# Regulators.net
KiCad netlist of a schematic drawn in Altium Designer
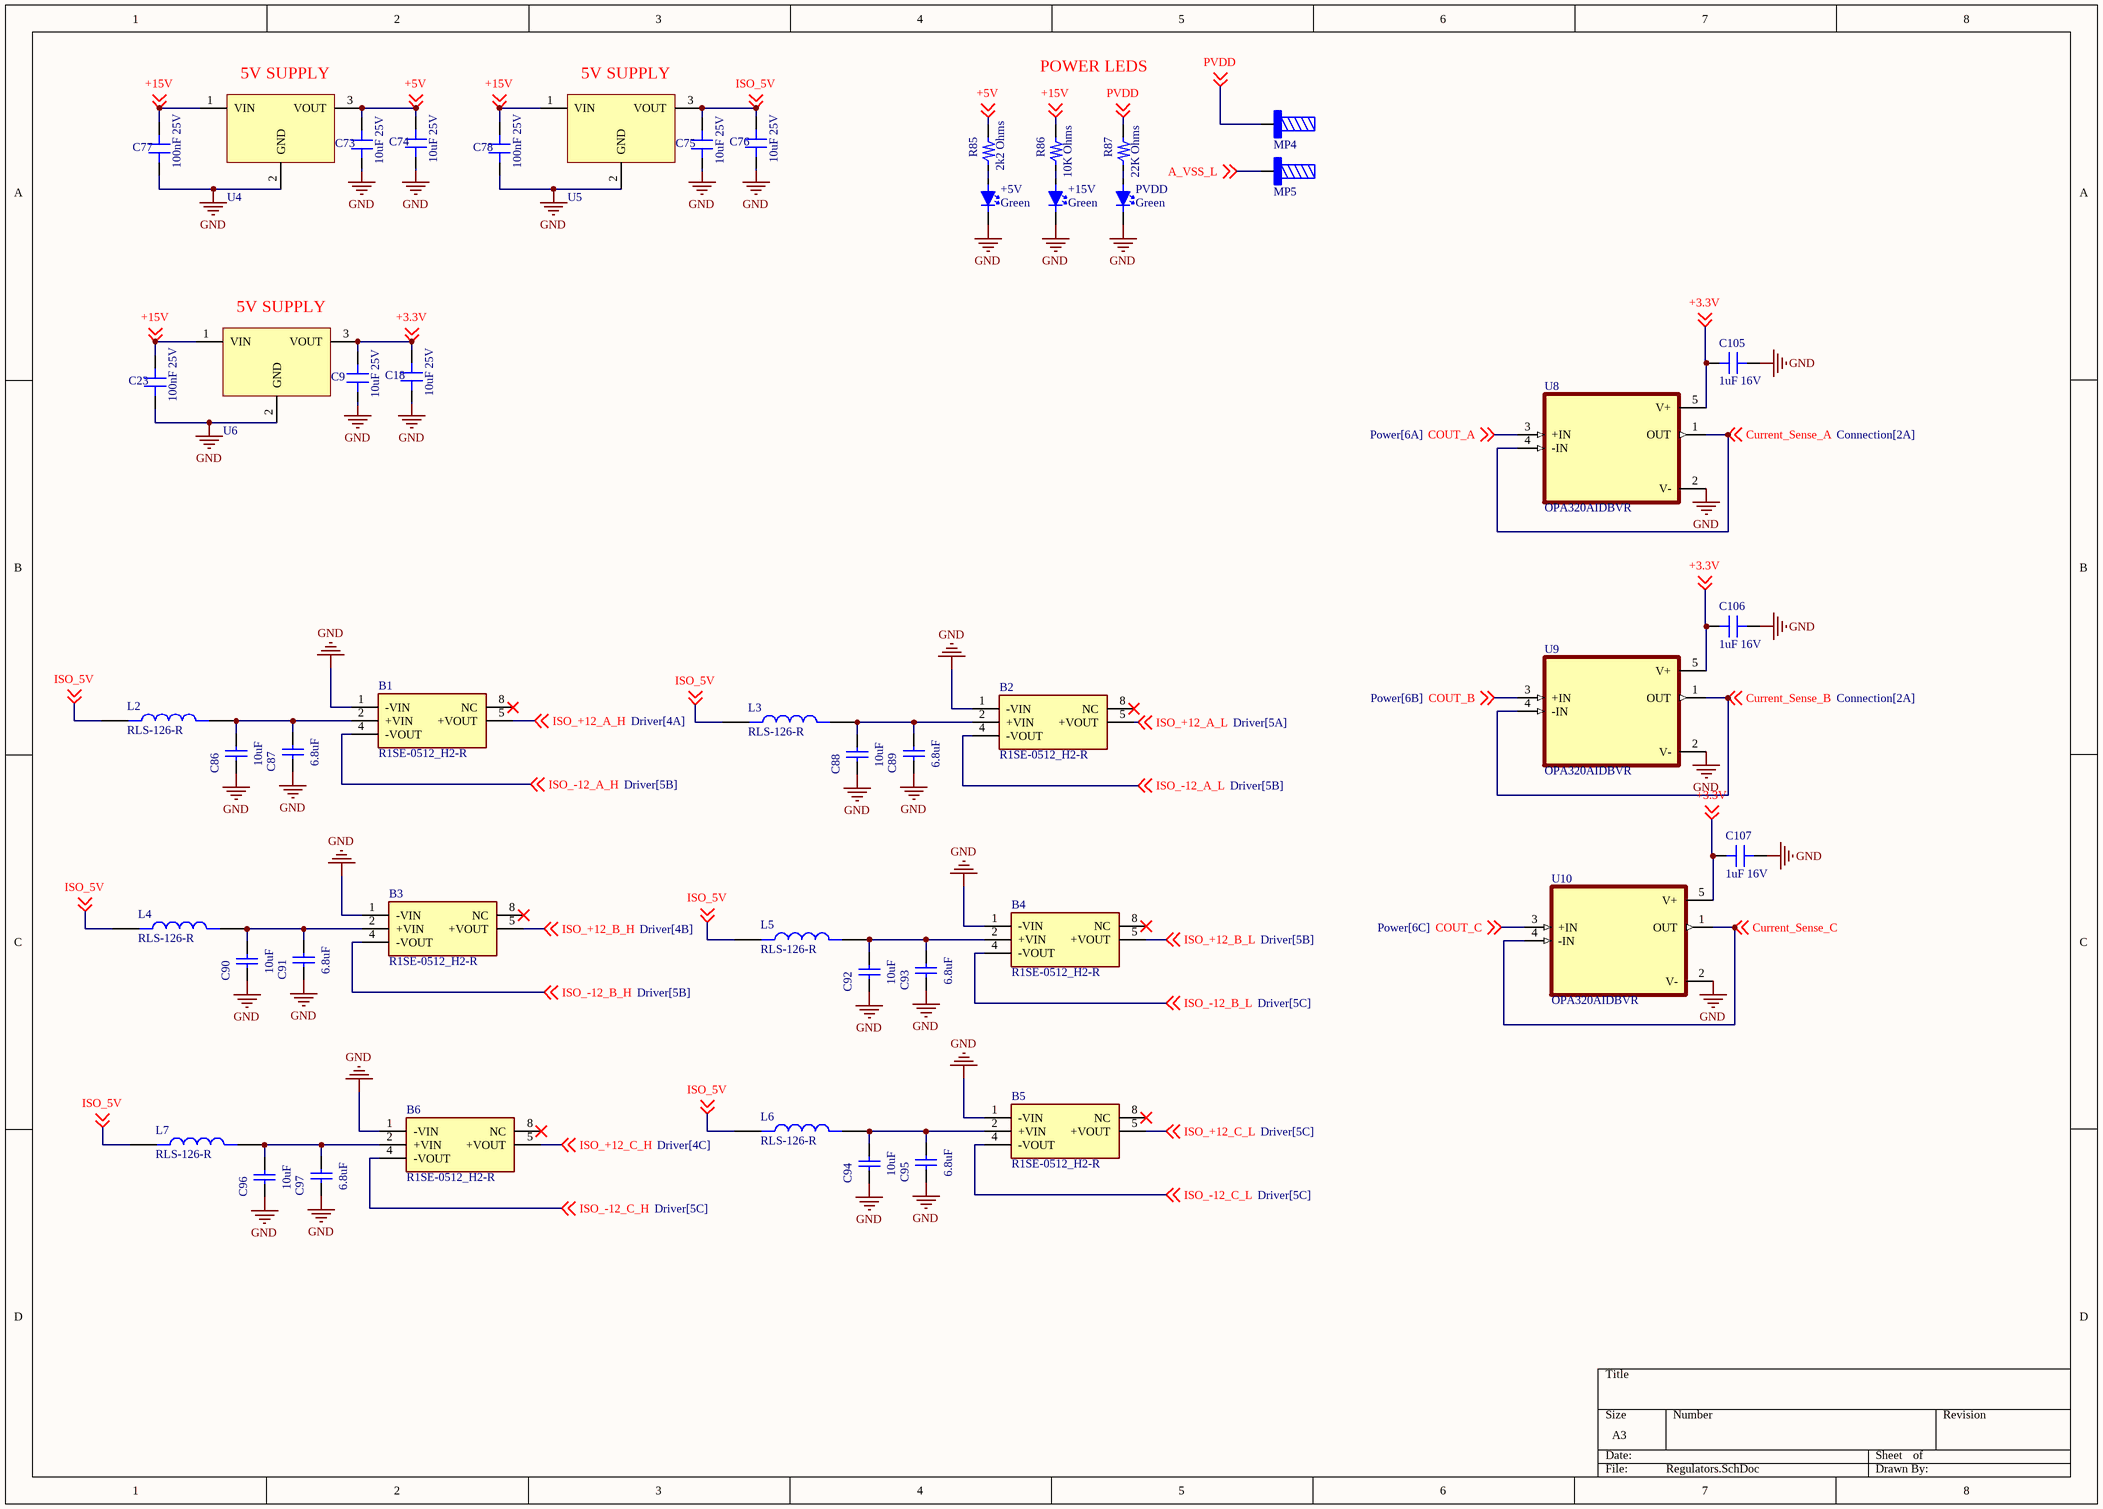
[diagram p0: Regulators.SchDoc]

(export (version "E")
  (design (tool "Eeschema 10.0.6"))
  (components
    (comp (ref "+5V")
      (value "Green")
      (footprint "0805LED")
      (description "0805")
      (libsource (lib "HidroanaSCHLib") (part "LED"))
    )
    (comp (ref "+15V")
      (value "Green")
      (footprint "0805LED")
      (description "0805")
      (libsource (lib "HidroanaSCHLib") (part "LED"))
    )
    (comp (ref "B1")
      (value "R1SE-0512_H2-R")
      (footprint "R1SE3305H2R")
      (description "RECOM POWER - R1SE-0512/H2-R - DC-DC CONVERTER, 12V, 0.084A, SMD")
      (fields
        (field (name "MANUFACTURER_PART_NUMBER") "R1SE-0512/H2-R")
        (field (name "MOUSER PART NUMBER") "919-R1SE-0512/H2-R")
      )
      (libsource (lib "R1SE-0512_H2-R") (part "R1SE-0512_H2-R"))
    )
    (comp (ref "B2")
      (value "R1SE-0512_H2-R")
      (footprint "R1SE3305H2R")
      (description "RECOM POWER - R1SE-0512/H2-R - DC-DC CONVERTER, 12V, 0.084A, SMD")
      (fields
        (field (name "MANUFACTURER_PART_NUMBER") "R1SE-0512/H2-R")
        (field (name "MOUSER PART NUMBER") "919-R1SE-0512/H2-R")
      )
      (libsource (lib "R1SE-0512_H2-R") (part "R1SE-0512_H2-R"))
    )
    (comp (ref "B3")
      (value "R1SE-0512_H2-R")
      (footprint "R1SE3305H2R")
      (description "RECOM POWER - R1SE-0512/H2-R - DC-DC CONVERTER, 12V, 0.084A, SMD")
      (fields
        (field (name "MANUFACTURER_PART_NUMBER") "R1SE-0512/H2-R")
        (field (name "MOUSER PART NUMBER") "919-R1SE-0512/H2-R")
      )
      (libsource (lib "R1SE-0512_H2-R") (part "R1SE-0512_H2-R"))
    )
    (comp (ref "B4")
      (value "R1SE-0512_H2-R")
      (footprint "R1SE3305H2R")
      (description "RECOM POWER - R1SE-0512/H2-R - DC-DC CONVERTER, 12V, 0.084A, SMD")
      (fields
        (field (name "MANUFACTURER_PART_NUMBER") "R1SE-0512/H2-R")
        (field (name "MOUSER PART NUMBER") "919-R1SE-0512/H2-R")
      )
      (libsource (lib "R1SE-0512_H2-R") (part "R1SE-0512_H2-R"))
    )
    (comp (ref "B5")
      (value "R1SE-0512_H2-R")
      (footprint "R1SE3305H2R")
      (description "RECOM POWER - R1SE-0512/H2-R - DC-DC CONVERTER, 12V, 0.084A, SMD")
      (fields
        (field (name "MANUFACTURER_PART_NUMBER") "R1SE-0512/H2-R")
        (field (name "MOUSER PART NUMBER") "919-R1SE-0512/H2-R")
      )
      (libsource (lib "R1SE-0512_H2-R") (part "R1SE-0512_H2-R"))
    )
    (comp (ref "B6")
      (value "R1SE-0512_H2-R")
      (footprint "R1SE3305H2R")
      (description "RECOM POWER - R1SE-0512/H2-R - DC-DC CONVERTER, 12V, 0.084A, SMD")
      (fields
        (field (name "MANUFACTURER_PART_NUMBER") "R1SE-0512/H2-R")
        (field (name "MOUSER PART NUMBER") "919-R1SE-0512/H2-R")
      )
      (libsource (lib "R1SE-0512_H2-R") (part "R1SE-0512_H2-R"))
    )
    (comp (ref "C9")
      (value "10uF 25V")
      (footprint "0603_CAP")
      (description "CL10B105KO8NNNC - MLCC (1608) 0603 1uF 16VDC ±10% X7R")
      (libsource (lib "HidroanaSCHLib") (part "CAP_0603"))
    )
    (comp (ref "C18")
      (value "10uF 25V")
      (footprint "0603_CAP")
      (description "CL10B105KO8NNNC - MLCC (1608) 0603 1uF 16VDC ±10% X7R")
      (libsource (lib "HidroanaSCHLib") (part "CAP_0603"))
    )
    (comp (ref "C23")
      (value "100nF 25V")
      (footprint "0603_CAP")
      (description "CL10B105KO8NNNC - MLCC (1608) 0603 1uF 16VDC ±10% X7R")
      (libsource (lib "HidroanaSCHLib") (part "CAP_0603"))
    )
    (comp (ref "C73")
      (value "10uF 25V")
      (footprint "0603_CAP")
      (description "CL10B105KO8NNNC - MLCC (1608) 0603 1uF 16VDC ±10% X7R")
      (libsource (lib "HidroanaSCHLib") (part "CAP_0603"))
    )
    (comp (ref "C74")
      (value "10uF 25V")
      (footprint "0603_CAP")
      (description "CL10B105KO8NNNC - MLCC (1608) 0603 1uF 16VDC ±10% X7R")
      (libsource (lib "HidroanaSCHLib") (part "CAP_0603"))
    )
    (comp (ref "C75")
      (value "10uF 25V")
      (footprint "0603_CAP")
      (description "CL10B105KO8NNNC - MLCC (1608) 0603 1uF 16VDC ±10% X7R")
      (libsource (lib "HidroanaSCHLib") (part "CAP_0603"))
    )
    (comp (ref "C76")
      (value "10uF 25V")
      (footprint "0603_CAP")
      (description "CL10B105KO8NNNC - MLCC (1608) 0603 1uF 16VDC ±10% X7R")
      (libsource (lib "HidroanaSCHLib") (part "CAP_0603"))
    )
    (comp (ref "C77")
      (value "100nF 25V")
      (footprint "0603_CAP")
      (description "CL10B105KO8NNNC - MLCC (1608) 0603 1uF 16VDC ±10% X7R")
      (libsource (lib "HidroanaSCHLib") (part "CAP_0603"))
    )
    (comp (ref "C78")
      (value "100nF 25V")
      (footprint "0603_CAP")
      (description "CL10B105KO8NNNC - MLCC (1608) 0603 1uF 16VDC ±10% X7R")
      (libsource (lib "HidroanaSCHLib") (part "CAP_0603"))
    )
    (comp (ref "C86")
      (value "10uF")
      (footprint "WCAP-CSGP_0805_L2W1.25H0.6_Reflow")
      (description "WCAP-CSGP Multilayer Ceramic Chip Capacitor, General Purpose, size 0805, NP0, 22pF, 16V")
      (fields
        (field (name "MANUFACTURER PART NUMBER") "885012007012")
        (field (name "MANUFACTURER") "Wurth Elektronik")
      )
      (libsource (lib "Altium_WCAP-CSGP (rev24c)") (part "885012007012"))
    )
    (comp (ref "C87")
      (value "6.8uF")
      (footprint "WCAP-CSGP_0805_L2W1.25H0.6_Reflow")
      (description "WCAP-CSGP Multilayer Ceramic Chip Capacitor, General Purpose, size 0805, NP0, 22pF, 16V")
      (fields
        (field (name "MANUFACTURER PART NUMBER") "885012007012")
        (field (name "MANUFACTURER") "Wurth Elektronik")
      )
      (libsource (lib "Altium_WCAP-CSGP (rev24c)") (part "885012007012"))
    )
    (comp (ref "C88")
      (value "10uF")
      (footprint "WCAP-CSGP_0805_L2W1.25H0.6_Reflow")
      (description "WCAP-CSGP Multilayer Ceramic Chip Capacitor, General Purpose, size 0805, NP0, 22pF, 16V")
      (fields
        (field (name "MANUFACTURER PART NUMBER") "885012007012")
        (field (name "MANUFACTURER") "Wurth Elektronik")
      )
      (libsource (lib "Altium_WCAP-CSGP (rev24c)") (part "885012007012"))
    )
    (comp (ref "C89")
      (value "6.8uF")
      (footprint "WCAP-CSGP_0805_L2W1.25H0.6_Reflow")
      (description "WCAP-CSGP Multilayer Ceramic Chip Capacitor, General Purpose, size 0805, NP0, 22pF, 16V")
      (fields
        (field (name "MANUFACTURER PART NUMBER") "885012007012")
        (field (name "MANUFACTURER") "Wurth Elektronik")
      )
      (libsource (lib "Altium_WCAP-CSGP (rev24c)") (part "885012007012"))
    )
    (comp (ref "C90")
      (value "10uF")
      (footprint "WCAP-CSGP_0805_L2W1.25H0.6_Reflow")
      (description "WCAP-CSGP Multilayer Ceramic Chip Capacitor, General Purpose, size 0805, NP0, 22pF, 16V")
      (fields
        (field (name "MANUFACTURER PART NUMBER") "885012007012")
        (field (name "MANUFACTURER") "Wurth Elektronik")
      )
      (libsource (lib "Altium_WCAP-CSGP (rev24c)") (part "885012007012"))
    )
    (comp (ref "C91")
      (value "6.8uF")
      (footprint "WCAP-CSGP_0805_L2W1.25H0.6_Reflow")
      (description "WCAP-CSGP Multilayer Ceramic Chip Capacitor, General Purpose, size 0805, NP0, 22pF, 16V")
      (fields
        (field (name "MANUFACTURER PART NUMBER") "885012007012")
        (field (name "MANUFACTURER") "Wurth Elektronik")
      )
      (libsource (lib "Altium_WCAP-CSGP (rev24c)") (part "885012007012"))
    )
    (comp (ref "C92")
      (value "10uF")
      (footprint "WCAP-CSGP_0805_L2W1.25H0.6_Reflow")
      (description "WCAP-CSGP Multilayer Ceramic Chip Capacitor, General Purpose, size 0805, NP0, 22pF, 16V")
      (fields
        (field (name "MANUFACTURER PART NUMBER") "885012007012")
        (field (name "MANUFACTURER") "Wurth Elektronik")
      )
      (libsource (lib "Altium_WCAP-CSGP (rev24c)") (part "885012007012"))
    )
    (comp (ref "C93")
      (value "6.8uF")
      (footprint "WCAP-CSGP_0805_L2W1.25H0.6_Reflow")
      (description "WCAP-CSGP Multilayer Ceramic Chip Capacitor, General Purpose, size 0805, NP0, 22pF, 16V")
      (fields
        (field (name "MANUFACTURER PART NUMBER") "885012007012")
        (field (name "MANUFACTURER") "Wurth Elektronik")
      )
      (libsource (lib "Altium_WCAP-CSGP (rev24c)") (part "885012007012"))
    )
    (comp (ref "C94")
      (value "10uF")
      (footprint "WCAP-CSGP_0805_L2W1.25H0.6_Reflow")
      (description "WCAP-CSGP Multilayer Ceramic Chip Capacitor, General Purpose, size 0805, NP0, 22pF, 16V")
      (fields
        (field (name "MANUFACTURER PART NUMBER") "885012007012")
        (field (name "MANUFACTURER") "Wurth Elektronik")
      )
      (libsource (lib "Altium_WCAP-CSGP (rev24c)") (part "885012007012"))
    )
    (comp (ref "C95")
      (value "6.8uF")
      (footprint "WCAP-CSGP_0805_L2W1.25H0.6_Reflow")
      (description "WCAP-CSGP Multilayer Ceramic Chip Capacitor, General Purpose, size 0805, NP0, 22pF, 16V")
      (fields
        (field (name "MANUFACTURER PART NUMBER") "885012007012")
        (field (name "MANUFACTURER") "Wurth Elektronik")
      )
      (libsource (lib "Altium_WCAP-CSGP (rev24c)") (part "885012007012"))
    )
    (comp (ref "C96")
      (value "10uF")
      (footprint "WCAP-CSGP_0805_L2W1.25H0.6_Reflow")
      (description "WCAP-CSGP Multilayer Ceramic Chip Capacitor, General Purpose, size 0805, NP0, 22pF, 16V")
      (fields
        (field (name "MANUFACTURER PART NUMBER") "885012007012")
        (field (name "MANUFACTURER") "Wurth Elektronik")
      )
      (libsource (lib "Altium_WCAP-CSGP (rev24c)") (part "885012007012"))
    )
    (comp (ref "C97")
      (value "6.8uF")
      (footprint "WCAP-CSGP_0805_L2W1.25H0.6_Reflow")
      (description "WCAP-CSGP Multilayer Ceramic Chip Capacitor, General Purpose, size 0805, NP0, 22pF, 16V")
      (fields
        (field (name "MANUFACTURER PART NUMBER") "885012007012")
        (field (name "MANUFACTURER") "Wurth Elektronik")
      )
      (libsource (lib "Altium_WCAP-CSGP (rev24c)") (part "885012007012"))
    )
    (comp (ref "C105")
      (value "1uF 16V")
      (footprint "0603_CAP")
      (description "CL10B105KO8NNNC - MLCC (1608) 0603 1uF 16VDC ±10% X7R")
      (libsource (lib "HidroanaSCHLib") (part "CAP_0603"))
    )
    (comp (ref "C106")
      (value "1uF 16V")
      (footprint "0603_CAP")
      (description "CL10B105KO8NNNC - MLCC (1608) 0603 1uF 16VDC ±10% X7R")
      (libsource (lib "HidroanaSCHLib") (part "CAP_0603"))
    )
    (comp (ref "C107")
      (value "1uF 16V")
      (footprint "0603_CAP")
      (description "CL10B105KO8NNNC - MLCC (1608) 0603 1uF 16VDC ±10% X7R")
      (libsource (lib "HidroanaSCHLib") (part "CAP_0603"))
    )
    (comp (ref "L2")
      (value "RLS-126-R")
      (footprint "IND_RLS-126-R")
      (description "Line Inductors for RECOM Power Supply")
      (fields (field (name "MF") "Recom Power"))
      (libsource (lib "RLS-126-R") (part "RLS-126-R"))
    )
    (comp (ref "L3")
      (value "RLS-126-R")
      (footprint "IND_RLS-126-R")
      (description "Line Inductors for RECOM Power Supply")
      (fields (field (name "MF") "Recom Power"))
      (libsource (lib "RLS-126-R") (part "RLS-126-R"))
    )
    (comp (ref "L4")
      (value "RLS-126-R")
      (footprint "IND_RLS-126-R")
      (description "Line Inductors for RECOM Power Supply")
      (fields (field (name "MF") "Recom Power"))
      (libsource (lib "RLS-126-R") (part "RLS-126-R"))
    )
    (comp (ref "L5")
      (value "RLS-126-R")
      (footprint "IND_RLS-126-R")
      (description "Line Inductors for RECOM Power Supply")
      (fields (field (name "MF") "Recom Power"))
      (libsource (lib "RLS-126-R") (part "RLS-126-R"))
    )
    (comp (ref "L6")
      (value "RLS-126-R")
      (footprint "IND_RLS-126-R")
      (description "Line Inductors for RECOM Power Supply")
      (fields (field (name "MF") "Recom Power"))
      (libsource (lib "RLS-126-R") (part "RLS-126-R"))
    )
    (comp (ref "L7")
      (value "RLS-126-R")
      (footprint "IND_RLS-126-R")
      (description "Line Inductors for RECOM Power Supply")
      (fields (field (name "MF") "Recom Power"))
      (libsource (lib "RLS-126-R") (part "RLS-126-R"))
    )
    (comp (ref "MP4")
      (value "M6 x 10mm")
      (footprint "7461098_chemical surface")
      (description "WP-SHFU REDCUBE PRESS-FIT with external thread, L13W13H15.5mm, M6 x 10mm, 250A")
      (fields
        (field (name "MANUFACTURER PART NUMBER") "7461098")
        (field (name "MANUFACTURER") "Wurth Elektronik")
      )
      (libsource (lib "Altium_WP-SHFU (rev22b)") (part "7461098"))
    )
    (comp (ref "MP5")
      (value "M6 x 10mm")
      (footprint "7461098_chemical surface")
      (description "WP-SHFU REDCUBE PRESS-FIT with external thread, L13W13H15.5mm, M6 x 10mm, 250A")
      (fields
        (field (name "MANUFACTURER PART NUMBER") "7461098")
        (field (name "MANUFACTURER") "Wurth Elektronik")
      )
      (libsource (lib "Altium_WP-SHFU (rev22b)") (part "7461098"))
    )
    (comp (ref "PVDD")
      (value "Green")
      (footprint "0805LED")
      (description "0805")
      (libsource (lib "HidroanaSCHLib") (part "LED"))
    )
    (comp (ref "R85")
      (value "2k2 Ohms")
      (footprint "0805_RES")
      (description "0805")
      (fields (field (name "POWER") "1/8 W"))
      (libsource (lib "HidroanaSCHLib") (part "RES_0805"))
    )
    (comp (ref "R86")
      (value "10K Ohms")
      (footprint "0805_RES")
      (description "0805")
      (fields (field (name "POWER") "1/8 W"))
      (libsource (lib "HidroanaSCHLib") (part "RES_0805"))
    )
    (comp (ref "R87")
      (value "22K Ohms")
      (footprint "0805_RES")
      (description "0805")
      (fields (field (name "POWER") "1/8 W"))
      (libsource (lib "HidroanaSCHLib") (part "RES_0805"))
    )
    (comp (ref "U4")
      (value "8-28Vin, 5Vout, 1Aout")
      (footprint "WPME-FDSM_SIP-3_L11.6W8.5H10.5")
      (description "WPME-FDSM Fixed Step Down Regulator Module, THT, SIP-3, 8-28Vin, 5Vout, 1Aout")
      (fields
        (field (name "MANUFACTURER PART NUMBER") "173010578")
        (field (name "MANUFACTURER") "Wurth Elektronik")
      )
      (libsource (lib "MagIC-FDSM (rev22e)") (part "173010578"))
    )
    (comp (ref "U5")
      (value "8-28Vin, 5Vout, 1Aout")
      (footprint "WPME-FDSM_SIP-3_L11.6W8.5H10.5")
      (description "WPME-FDSM Fixed Step Down Regulator Module, THT, SIP-3, 8-28Vin, 5Vout, 1Aout")
      (fields
        (field (name "MANUFACTURER PART NUMBER") "173010578")
        (field (name "MANUFACTURER") "Wurth Elektronik")
      )
      (libsource (lib "MagIC-FDSM (rev22e)") (part "173010578"))
    )
    (comp (ref "U6")
      (value "8-28Vin, 5Vout, 1Aout")
      (footprint "WPME-FDSM_SIP-3_L11.6W8.5H10.5")
      (description "WPME-FDSM Fixed Step Down Regulator Module, THT, SIP-3, 8-28Vin, 5Vout, 1Aout")
      (fields
        (field (name "MANUFACTURER PART NUMBER") "173010578")
        (field (name "MANUFACTURER") "Wurth Elektronik")
      )
      (libsource (lib "MagIC-FDSM (rev22e)") (part "173010578"))
    )
    (comp (ref "U8")
      (value "OPA320AIDBVR")
      (footprint "SOT95P280X145-5N")
      (description "Precision, zero-crossover, 20-MHz, 0.9-pA Ib, RRIO, CMOS operational amplifier")
      (fields (field (name "MF") "Texas Instruments"))
      (libsource (lib "OPA320AIDBVR") (part "OPA320AIDBVR"))
    )
    (comp (ref "U9")
      (value "OPA320AIDBVR")
      (footprint "SOT95P280X145-5N")
      (description "Precision, zero-crossover, 20-MHz, 0.9-pA Ib, RRIO, CMOS operational amplifier")
      (fields (field (name "MF") "Texas Instruments"))
      (libsource (lib "OPA320AIDBVR") (part "OPA320AIDBVR"))
    )
    (comp (ref "U10")
      (value "OPA320AIDBVR")
      (footprint "SOT95P280X145-5N")
      (description "Precision, zero-crossover, 20-MHz, 0.9-pA Ib, RRIO, CMOS operational amplifier")
      (fields (field (name "MF") "Texas Instruments"))
      (libsource (lib "OPA320AIDBVR") (part "OPA320AIDBVR"))
    )
  )
  (nets
    (net (code "1") (name "+3.3V") (class "Default")
      (node (ref "C105") (pin "1") (pinfunction "1_1") (pintype "passive"))
      (node (ref "C106") (pin "1") (pinfunction "1_1") (pintype "passive"))
      (node (ref "C107") (pin "1") (pinfunction "1_1") (pintype "passive"))
      (node (ref "C18") (pin "2") (pinfunction "2_2") (pintype "passive"))
      (node (ref "C9") (pin "2") (pinfunction "2_2") (pintype "passive"))
      (node (ref "U10") (pin "5") (pinfunction "V+_5") (pintype "power_in"))
      (node (ref "U6") (pin "3") (pinfunction "VOUT_3") (pintype "passive"))
      (node (ref "U8") (pin "5") (pinfunction "V+_5") (pintype "power_in"))
      (node (ref "U9") (pin "5") (pinfunction "V+_5") (pintype "power_in"))
    )
    (net (code "2") (name "+5V") (class "Default")
      (node (ref "C73") (pin "2") (pinfunction "2_2") (pintype "passive"))
      (node (ref "C74") (pin "2") (pinfunction "2_2") (pintype "passive"))
      (node (ref "R85") (pin "1") (pintype "passive"))
      (node (ref "U4") (pin "3") (pinfunction "VOUT_3") (pintype "passive"))
    )
    (net (code "3") (name "+15V") (class "Default")
      (node (ref "C23") (pin "2") (pinfunction "2_2") (pintype "passive"))
      (node (ref "C77") (pin "2") (pinfunction "2_2") (pintype "passive"))
      (node (ref "C78") (pin "2") (pinfunction "2_2") (pintype "passive"))
      (node (ref "R86") (pin "1") (pintype "passive"))
      (node (ref "U4") (pin "1") (pinfunction "VIN_1") (pintype "passive"))
      (node (ref "U5") (pin "1") (pinfunction "VIN_1") (pintype "passive"))
      (node (ref "U6") (pin "1") (pinfunction "VIN_1") (pintype "passive"))
    )
    (net (code "4") (name "A_VSS_L") (class "Default")
      (node (ref "MP5") (pin "1") (pinfunction "1_1") (pintype "passive"))
    )
    (net (code "5") (name "COUT_A") (class "Default")
      (node (ref "U8") (pin "3") (pinfunction "+IN_3") (pintype "input"))
    )
    (net (code "6") (name "COUT_B") (class "Default")
      (node (ref "U9") (pin "3") (pinfunction "+IN_3") (pintype "input"))
    )
    (net (code "7") (name "COUT_C") (class "Default")
      (node (ref "U10") (pin "3") (pinfunction "+IN_3") (pintype "input"))
    )
    (net (code "8") (name "Current_Sense_A") (class "Default")
      (node (ref "U8") (pin "1") (pinfunction "OUT_1") (pintype "output"))
      (node (ref "U8") (pin "4") (pinfunction "-IN_4") (pintype "input"))
    )
    (net (code "9") (name "Current_Sense_B") (class "Default")
      (node (ref "U9") (pin "1") (pinfunction "OUT_1") (pintype "output"))
      (node (ref "U9") (pin "4") (pinfunction "-IN_4") (pintype "input"))
    )
    (net (code "10") (name "Current_Sense_C") (class "Default")
      (node (ref "U10") (pin "1") (pinfunction "OUT_1") (pintype "output"))
      (node (ref "U10") (pin "4") (pinfunction "-IN_4") (pintype "input"))
    )
    (net (code "11") (name "GND") (class "Default")
      (node (ref "+15V") (pin "2") (pinfunction "Cathode(-)_2") (pintype "passive"))
      (node (ref "+5V") (pin "2") (pinfunction "Cathode(-)_2") (pintype "passive"))
      (node (ref "B1") (pin "1") (pinfunction "-VIN_1") (pintype "passive"))
      (node (ref "B2") (pin "1") (pinfunction "-VIN_1") (pintype "passive"))
      (node (ref "B3") (pin "1") (pinfunction "-VIN_1") (pintype "passive"))
      (node (ref "B4") (pin "1") (pinfunction "-VIN_1") (pintype "passive"))
      (node (ref "B5") (pin "1") (pinfunction "-VIN_1") (pintype "passive"))
      (node (ref "B6") (pin "1") (pinfunction "-VIN_1") (pintype "passive"))
      (node (ref "C105") (pin "2") (pinfunction "2_2") (pintype "passive"))
      (node (ref "C106") (pin "2") (pinfunction "2_2") (pintype "passive"))
      (node (ref "C107") (pin "2") (pinfunction "2_2") (pintype "passive"))
      (node (ref "C18") (pin "1") (pinfunction "1_1") (pintype "passive"))
      (node (ref "C23") (pin "1") (pinfunction "1_1") (pintype "passive"))
      (node (ref "C73") (pin "1") (pinfunction "1_1") (pintype "passive"))
      (node (ref "C74") (pin "1") (pinfunction "1_1") (pintype "passive"))
      (node (ref "C75") (pin "1") (pinfunction "1_1") (pintype "passive"))
      (node (ref "C76") (pin "1") (pinfunction "1_1") (pintype "passive"))
      (node (ref "C77") (pin "1") (pinfunction "1_1") (pintype "passive"))
      (node (ref "C78") (pin "1") (pinfunction "1_1") (pintype "passive"))
      (node (ref "C86") (pin "1") (pinfunction "1_1") (pintype "passive"))
      (node (ref "C87") (pin "1") (pinfunction "1_1") (pintype "passive"))
      (node (ref "C88") (pin "1") (pinfunction "1_1") (pintype "passive"))
      (node (ref "C89") (pin "1") (pinfunction "1_1") (pintype "passive"))
      (node (ref "C9") (pin "1") (pinfunction "1_1") (pintype "passive"))
      (node (ref "C90") (pin "1") (pinfunction "1_1") (pintype "passive"))
      (node (ref "C91") (pin "1") (pinfunction "1_1") (pintype "passive"))
      (node (ref "C92") (pin "1") (pinfunction "1_1") (pintype "passive"))
      (node (ref "C93") (pin "1") (pinfunction "1_1") (pintype "passive"))
      (node (ref "C94") (pin "1") (pinfunction "1_1") (pintype "passive"))
      (node (ref "C95") (pin "1") (pinfunction "1_1") (pintype "passive"))
      (node (ref "C96") (pin "1") (pinfunction "1_1") (pintype "passive"))
      (node (ref "C97") (pin "1") (pinfunction "1_1") (pintype "passive"))
      (node (ref "PVDD") (pin "2") (pinfunction "Cathode(-)_2") (pintype "passive"))
      (node (ref "U10") (pin "2") (pinfunction "V-_2") (pintype "power_in"))
      (node (ref "U4") (pin "2") (pinfunction "GND_2") (pintype "passive"))
      (node (ref "U5") (pin "2") (pinfunction "GND_2") (pintype "passive"))
      (node (ref "U6") (pin "2") (pinfunction "GND_2") (pintype "passive"))
      (node (ref "U8") (pin "2") (pinfunction "V-_2") (pintype "power_in"))
      (node (ref "U9") (pin "2") (pinfunction "V-_2") (pintype "power_in"))
    )
    (net (code "12") (name "ISO_+12_A_H") (class "Default")
      (node (ref "B1") (pin "5") (pinfunction "+VOUT_5") (pintype "passive"))
    )
    (net (code "13") (name "ISO_+12_A_L") (class "Default")
      (node (ref "B2") (pin "5") (pinfunction "+VOUT_5") (pintype "passive"))
    )
    (net (code "14") (name "ISO_+12_B_H") (class "Default")
      (node (ref "B3") (pin "5") (pinfunction "+VOUT_5") (pintype "passive"))
    )
    (net (code "15") (name "ISO_+12_B_L") (class "Default")
      (node (ref "B4") (pin "5") (pinfunction "+VOUT_5") (pintype "passive"))
    )
    (net (code "16") (name "ISO_+12_C_H") (class "Default")
      (node (ref "B6") (pin "5") (pinfunction "+VOUT_5") (pintype "passive"))
    )
    (net (code "17") (name "ISO_+12_C_L") (class "Default")
      (node (ref "B5") (pin "5") (pinfunction "+VOUT_5") (pintype "passive"))
    )
    (net (code "18") (name "ISO_-12_A_H") (class "Default")
      (node (ref "B1") (pin "4") (pinfunction "-VOUT_4") (pintype "passive"))
    )
    (net (code "19") (name "ISO_-12_A_L") (class "Default")
      (node (ref "B2") (pin "4") (pinfunction "-VOUT_4") (pintype "passive"))
    )
    (net (code "20") (name "ISO_-12_B_H") (class "Default")
      (node (ref "B3") (pin "4") (pinfunction "-VOUT_4") (pintype "passive"))
    )
    (net (code "21") (name "ISO_-12_B_L") (class "Default")
      (node (ref "B4") (pin "4") (pinfunction "-VOUT_4") (pintype "passive"))
    )
    (net (code "22") (name "ISO_-12_C_H") (class "Default")
      (node (ref "B6") (pin "4") (pinfunction "-VOUT_4") (pintype "passive"))
    )
    (net (code "23") (name "ISO_-12_C_L") (class "Default")
      (node (ref "B5") (pin "4") (pinfunction "-VOUT_4") (pintype "passive"))
    )
    (net (code "24") (name "ISO_5V") (class "Default")
      (node (ref "C75") (pin "2") (pinfunction "2_2") (pintype "passive"))
      (node (ref "C76") (pin "2") (pinfunction "2_2") (pintype "passive"))
      (node (ref "L2") (pin "1") (pinfunction "1_1") (pintype "passive"))
      (node (ref "L3") (pin "1") (pinfunction "1_1") (pintype "passive"))
      (node (ref "L4") (pin "1") (pinfunction "1_1") (pintype "passive"))
      (node (ref "L5") (pin "1") (pinfunction "1_1") (pintype "passive"))
      (node (ref "L6") (pin "1") (pinfunction "1_1") (pintype "passive"))
      (node (ref "L7") (pin "1") (pinfunction "1_1") (pintype "passive"))
      (node (ref "U5") (pin "3") (pinfunction "VOUT_3") (pintype "passive"))
    )
    (net (code "25") (name "Net-(+5V-Anode(+))") (class "Default")
      (node (ref "+5V") (pin "1") (pinfunction "Anode(+)_1") (pintype "passive"))
      (node (ref "R85") (pin "2") (pintype "passive"))
    )
    (net (code "26") (name "Net-(+15V-Anode(+))") (class "Default")
      (node (ref "+15V") (pin "1") (pinfunction "Anode(+)_1") (pintype "passive"))
      (node (ref "R86") (pin "2") (pintype "passive"))
    )
    (net (code "27") (name "Net-(B1-+VIN)") (class "Default")
      (node (ref "B1") (pin "2") (pinfunction "+VIN_2") (pintype "passive"))
      (node (ref "C86") (pin "2") (pinfunction "2_2") (pintype "passive"))
      (node (ref "C87") (pin "2") (pinfunction "2_2") (pintype "passive"))
      (node (ref "L2") (pin "2") (pinfunction "2_2") (pintype "passive"))
    )
    (net (code "28") (name "Net-(B2-+VIN)") (class "Default")
      (node (ref "B2") (pin "2") (pinfunction "+VIN_2") (pintype "passive"))
      (node (ref "C88") (pin "2") (pinfunction "2_2") (pintype "passive"))
      (node (ref "C89") (pin "2") (pinfunction "2_2") (pintype "passive"))
      (node (ref "L3") (pin "2") (pinfunction "2_2") (pintype "passive"))
    )
    (net (code "29") (name "Net-(B3-+VIN)") (class "Default")
      (node (ref "B3") (pin "2") (pinfunction "+VIN_2") (pintype "passive"))
      (node (ref "C90") (pin "2") (pinfunction "2_2") (pintype "passive"))
      (node (ref "C91") (pin "2") (pinfunction "2_2") (pintype "passive"))
      (node (ref "L4") (pin "2") (pinfunction "2_2") (pintype "passive"))
    )
    (net (code "30") (name "Net-(B4-+VIN)") (class "Default")
      (node (ref "B4") (pin "2") (pinfunction "+VIN_2") (pintype "passive"))
      (node (ref "C92") (pin "2") (pinfunction "2_2") (pintype "passive"))
      (node (ref "C93") (pin "2") (pinfunction "2_2") (pintype "passive"))
      (node (ref "L5") (pin "2") (pinfunction "2_2") (pintype "passive"))
    )
    (net (code "31") (name "Net-(B5-+VIN)") (class "Default")
      (node (ref "B5") (pin "2") (pinfunction "+VIN_2") (pintype "passive"))
      (node (ref "C94") (pin "2") (pinfunction "2_2") (pintype "passive"))
      (node (ref "C95") (pin "2") (pinfunction "2_2") (pintype "passive"))
      (node (ref "L6") (pin "2") (pinfunction "2_2") (pintype "passive"))
    )
    (net (code "32") (name "Net-(B6-+VIN)") (class "Default")
      (node (ref "B6") (pin "2") (pinfunction "+VIN_2") (pintype "passive"))
      (node (ref "C96") (pin "2") (pinfunction "2_2") (pintype "passive"))
      (node (ref "C97") (pin "2") (pinfunction "2_2") (pintype "passive"))
      (node (ref "L7") (pin "2") (pinfunction "2_2") (pintype "passive"))
    )
    (net (code "33") (name "Net-(PVDD-Anode(+))") (class "Default")
      (node (ref "PVDD") (pin "1") (pinfunction "Anode(+)_1") (pintype "passive"))
      (node (ref "R87") (pin "2") (pintype "passive"))
    )
    (net (code "34") (name "PVDD") (class "Default")
      (node (ref "MP4") (pin "1") (pinfunction "1_1") (pintype "passive"))
      (node (ref "R87") (pin "1") (pintype "passive"))
    )
    (net (code "35") (name "unconnected-(B1-NC-Pad8)") (class "Default")
      (node (ref "B1") (pin "8") (pinfunction "NC_8") (pintype "passive+no_connect"))
    )
    (net (code "36") (name "unconnected-(B2-NC-Pad8)") (class "Default")
      (node (ref "B2") (pin "8") (pinfunction "NC_8") (pintype "passive+no_connect"))
    )
    (net (code "37") (name "unconnected-(B3-NC-Pad8)") (class "Default")
      (node (ref "B3") (pin "8") (pinfunction "NC_8") (pintype "passive+no_connect"))
    )
    (net (code "38") (name "unconnected-(B4-NC-Pad8)") (class "Default")
      (node (ref "B4") (pin "8") (pinfunction "NC_8") (pintype "passive+no_connect"))
    )
    (net (code "39") (name "unconnected-(B5-NC-Pad8)") (class "Default")
      (node (ref "B5") (pin "8") (pinfunction "NC_8") (pintype "passive+no_connect"))
    )
    (net (code "40") (name "unconnected-(B6-NC-Pad8)") (class "Default")
      (node (ref "B6") (pin "8") (pinfunction "NC_8") (pintype "passive+no_connect"))
    )
  )
)
